# THQRight_Throttle_Hat_Board.net
KiCad netlist of a schematic drawn in EasyEDA
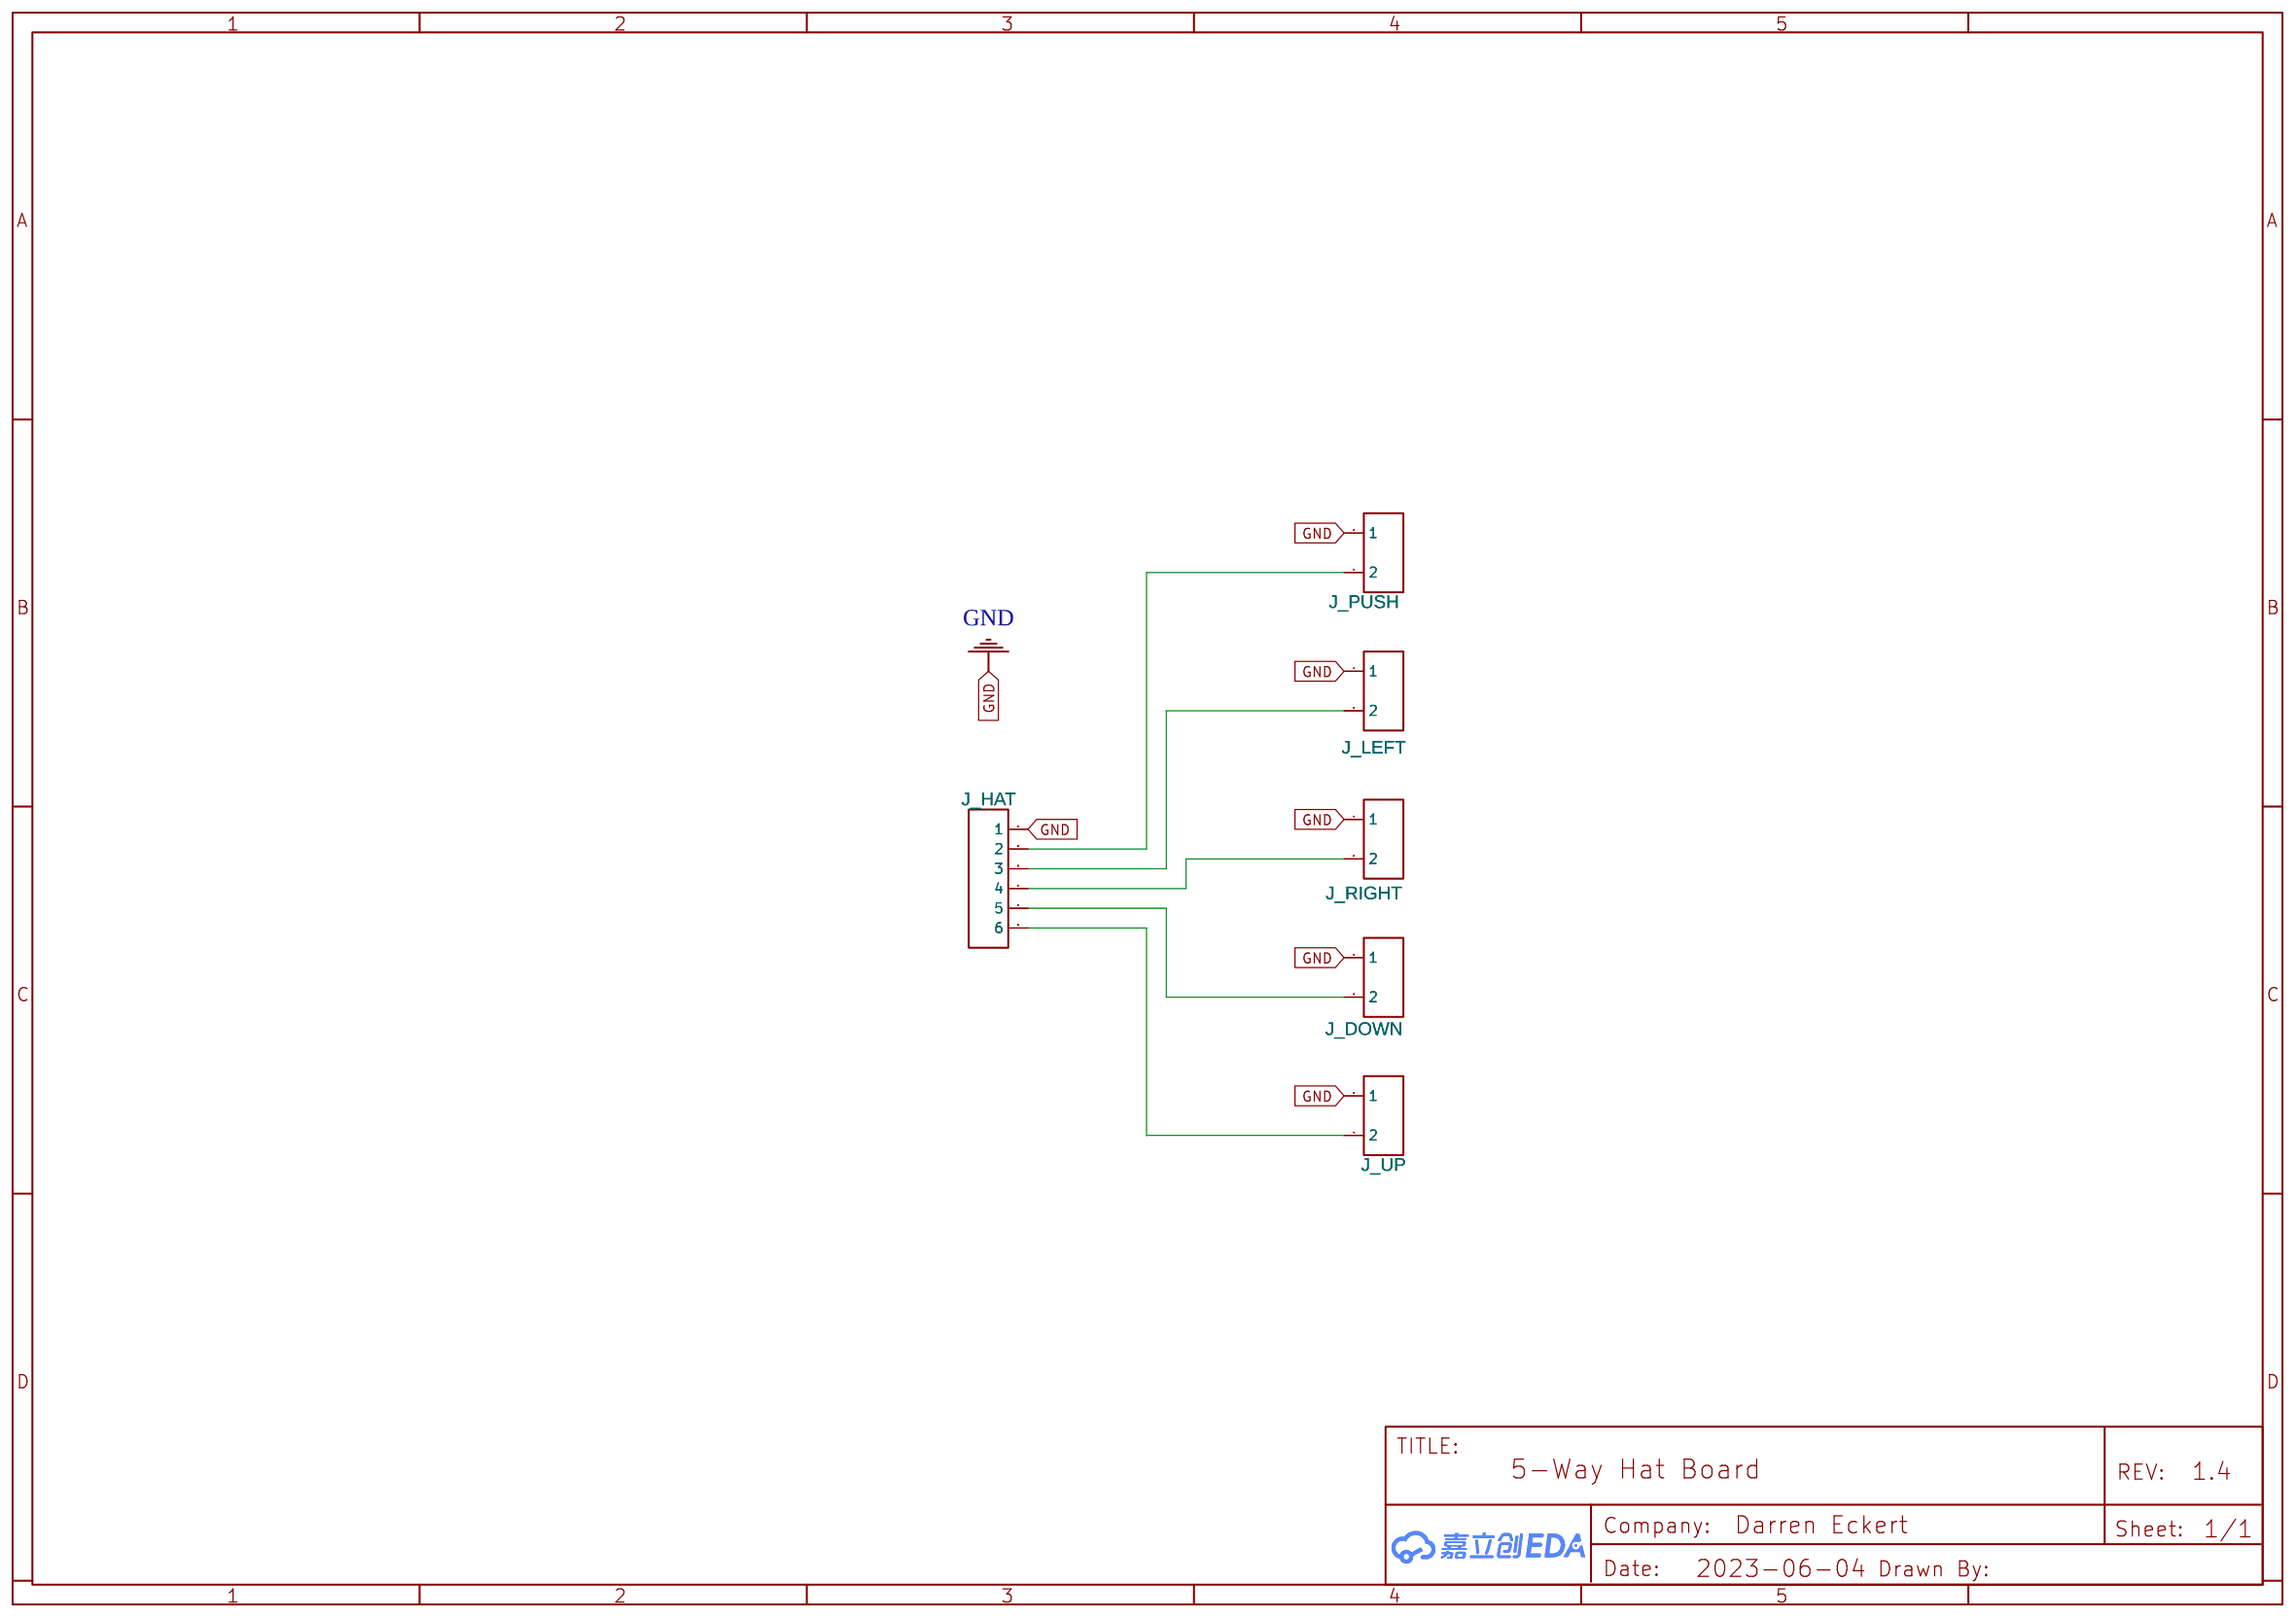
[diagram p0: schematic sheet]

(export (version "E")
  (design (tool "Eeschema 10.0.6"))
  (components
    (comp (ref "J_DOWN")
      (value "Header-Male-2.54_1x2")
      (fields (field (name "BOM_Manufacturer Part") "826629-2") (field (name "BOM_Supplier Part") "C86471"))
      (libsource (lib "") (part "Header-Male-2.54_1x2_3"))
    )
    (comp (ref "J_HAT")
      (value "Header-Male-2.54_1x6")
      (fields
        (field (name "BOM_Manufacturer Part") "2.54-1x6P直针")
        (field (name "BOM_Supplier Part") "C37208")
      )
      (libsource (lib "") (part "Header-Male-2.54_1x6"))
    )
    (comp (ref "J_LEFT")
      (value "Header-Male-2.54_1x2")
      (fields (field (name "BOM_Manufacturer Part") "826629-2") (field (name "BOM_Supplier Part") "C86471"))
      (libsource (lib "") (part "Header-Male-2.54_1x2_4"))
    )
    (comp (ref "J_PUSH")
      (value "Header-Male-2.54_1x2")
      (fields (field (name "BOM_Manufacturer Part") "826629-2") (field (name "BOM_Supplier Part") "C86471"))
      (libsource (lib "") (part "Header-Male-2.54_1x2"))
    )
    (comp (ref "J_RIGHT")
      (value "Header-Male-2.54_1x2")
      (fields (field (name "BOM_Manufacturer Part") "826629-2") (field (name "BOM_Supplier Part") "C86471"))
      (libsource (lib "") (part "Header-Male-2.54_1x2_2"))
    )
    (comp (ref "J_UP")
      (value "Header-Male-2.54_1x2")
      (fields (field (name "BOM_Manufacturer Part") "826629-2") (field (name "BOM_Supplier Part") "C86471"))
      (libsource (lib "") (part "Header-Male-2.54_1x2_1"))
    )
  )
  (nets
    (net (code "1") (name "GND") (class "Default")
      (node (ref "J_DOWN") (pin "1") (pinfunction "1_1") (pintype "unspecified"))
      (node (ref "J_HAT") (pin "1") (pinfunction "1_1") (pintype "input"))
      (node (ref "J_LEFT") (pin "1") (pinfunction "1_1") (pintype "unspecified"))
      (node (ref "J_PUSH") (pin "1") (pinfunction "1_1") (pintype "unspecified"))
      (node (ref "J_RIGHT") (pin "1") (pinfunction "1_1") (pintype "unspecified"))
      (node (ref "J_UP") (pin "1") (pinfunction "1_1") (pintype "unspecified"))
    )
    (net (code "2") (name "Net-(J_DOWN-Pad2)") (class "Default")
      (node (ref "J_DOWN") (pin "2") (pinfunction "2_2") (pintype "unspecified"))
      (node (ref "J_HAT") (pin "5") (pinfunction "5_5") (pintype "input"))
    )
    (net (code "3") (name "Net-(J_HAT-Pad2)") (class "Default")
      (node (ref "J_HAT") (pin "2") (pinfunction "2_2") (pintype "input"))
      (node (ref "J_PUSH") (pin "2") (pinfunction "2_2") (pintype "unspecified"))
    )
    (net (code "4") (name "Net-(J_HAT-Pad3)") (class "Default")
      (node (ref "J_HAT") (pin "3") (pinfunction "3_3") (pintype "input"))
      (node (ref "J_LEFT") (pin "2") (pinfunction "2_2") (pintype "unspecified"))
    )
    (net (code "5") (name "Net-(J_HAT-Pad4)") (class "Default")
      (node (ref "J_HAT") (pin "4") (pinfunction "4_4") (pintype "input"))
      (node (ref "J_RIGHT") (pin "2") (pinfunction "2_2") (pintype "unspecified"))
    )
    (net (code "6") (name "Net-(J_HAT-Pad6)") (class "Default")
      (node (ref "J_HAT") (pin "6") (pinfunction "6_6") (pintype "input"))
      (node (ref "J_UP") (pin "2") (pinfunction "2_2") (pintype "unspecified"))
    )
  )
)
